# Interfaz_RS232.net
KiCad netlist of a schematic drawn in Altium Designer
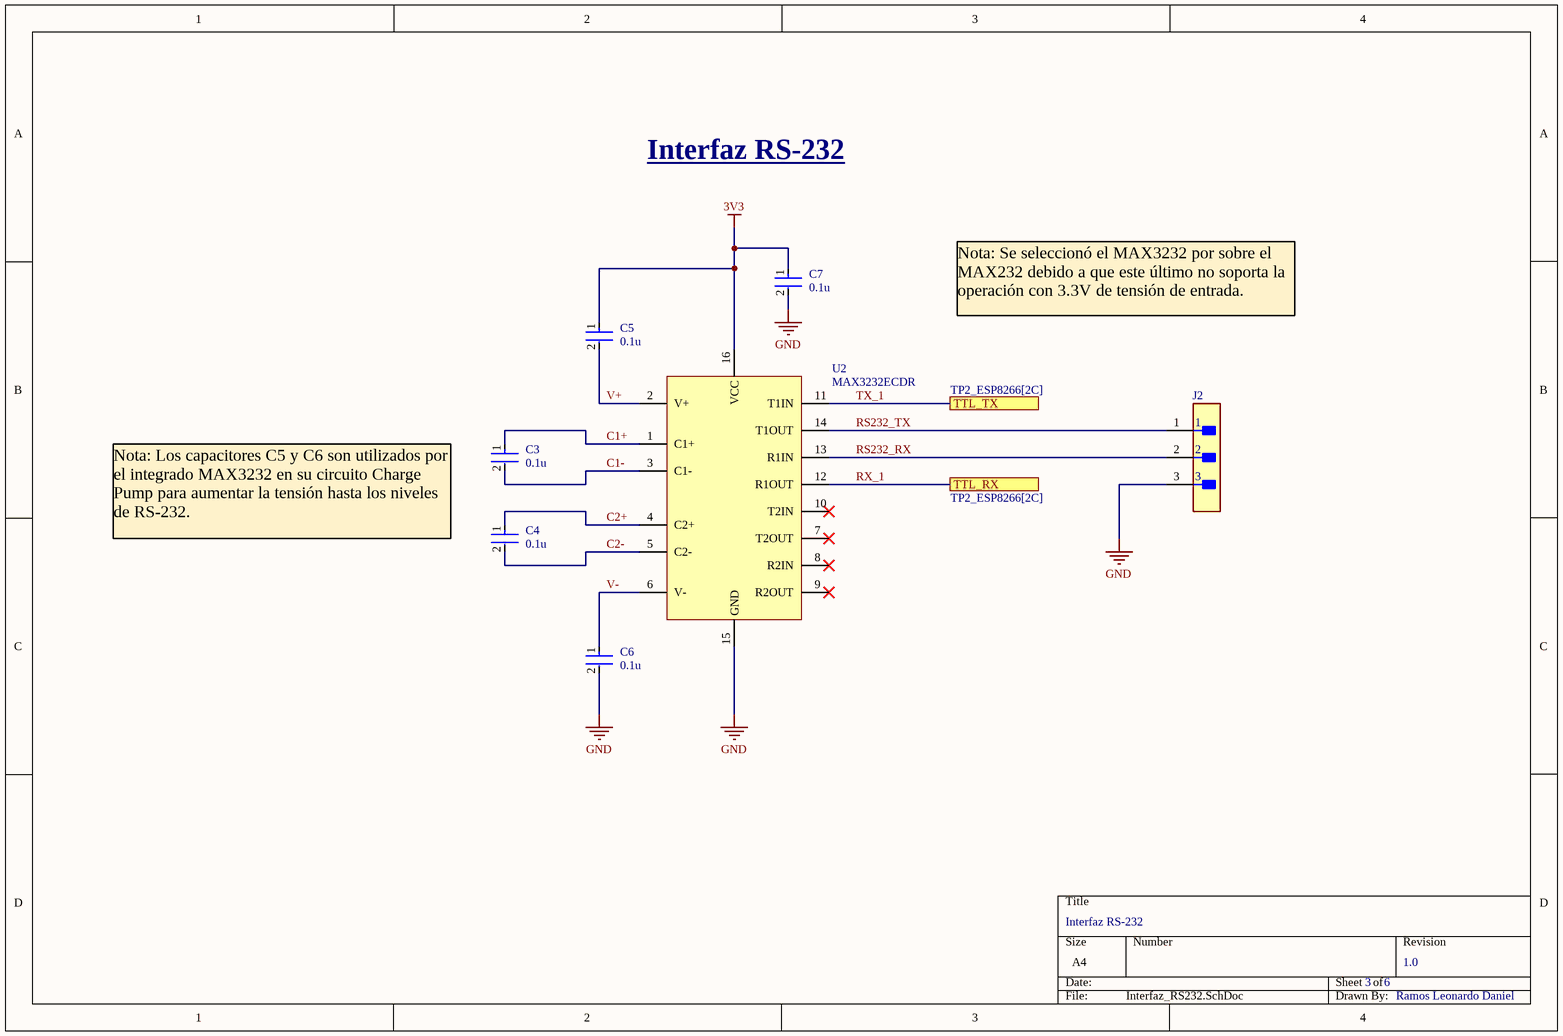
[diagram p0: Interfaz_RS232.SchDoc]

(export (version "E")
  (design (tool "Eeschema 10.0.6"))
  (components
    (comp (ref "C3")
      (value "0.1u")
      (footprint "FP-CC0805-0_85-MFG")
      (description "CAP CER 0.1UF 25V X7R 0805")
      (fields (field (name "MANUFACTURER PART NUMBER") "CC0805KRX7R8BB104") (field (name "TOLERANCE") "0.1"))
      (libsource (lib "Altium Content Vault") (part "11868f565c42a9108669ba33697ecf6"))
    )
    (comp (ref "C4")
      (value "0.1u")
      (footprint "FP-CC0805-0_85-MFG")
      (description "CAP CER 0.1UF 25V X7R 0805")
      (fields (field (name "MANUFACTURER PART NUMBER") "CC0805KRX7R8BB104") (field (name "TOLERANCE") "0.1"))
      (libsource (lib "Altium Content Vault") (part "11868f565c42a9108669ba33697ecf6"))
    )
    (comp (ref "C5")
      (value "0.1u")
      (footprint "FP-CC0805-0_85-MFG")
      (description "CAP CER 0.1UF 25V X7R 0805")
      (fields (field (name "MANUFACTURER PART NUMBER") "CC0805KRX7R8BB104") (field (name "TOLERANCE") "0.1"))
      (libsource (lib "Altium Content Vault") (part "11868f565c42a9108669ba33697ecf6"))
    )
    (comp (ref "C6")
      (value "0.1u")
      (footprint "FP-CC0805-0_85-MFG")
      (description "CAP CER 0.1UF 25V X7R 0805")
      (fields (field (name "MANUFACTURER PART NUMBER") "CC0805KRX7R8BB104") (field (name "TOLERANCE") "0.1"))
      (libsource (lib "Altium Content Vault") (part "11868f565c42a9108669ba33697ecf6"))
    )
    (comp (ref "C7")
      (value "0.1u")
      (footprint "FP-CC0805-0_85-MFG")
      (description "CAP CER 0.1UF 25V X7R 0805")
      (fields (field (name "MANUFACTURER PART NUMBER") "CC0805KRX7R8BB104") (field (name "TOLERANCE") "0.1"))
      (libsource (lib "Altium Content Vault") (part "11868f565c42a9108669ba33697ecf6"))
    )
    (comp (ref "J2")
      (value "22-11-1031")
      (footprint "FP-0022111031-MFG")
      (libsource (lib "Altium Content Vault") (part "0d3f023dd272f625e17a2be33dea85f"))
    )
    (comp (ref "U2")
      (value "MAX3232ECDR")
      (footprint "D0016A_M")
      (libsource (lib "Miscelaneos") (part "MAX3232ECDR"))
    )
  )
  (nets
    (net (code "1") (name "/C1+") (class "Default")
      (node (ref "C3") (pin "1") (pinfunction "1_1") (pintype "passive"))
      (node (ref "U2") (pin "1") (pinfunction "C1+_1") (pintype "passive"))
    )
    (net (code "2") (name "/C1-") (class "Default")
      (node (ref "C3") (pin "2") (pinfunction "2_2") (pintype "passive"))
      (node (ref "U2") (pin "3") (pinfunction "C1-_3") (pintype "passive"))
    )
    (net (code "3") (name "/C2+") (class "Default")
      (node (ref "C4") (pin "1") (pinfunction "1_1") (pintype "passive"))
      (node (ref "U2") (pin "4") (pinfunction "C2+_4") (pintype "passive"))
    )
    (net (code "4") (name "/C2-") (class "Default")
      (node (ref "C4") (pin "2") (pinfunction "2_2") (pintype "passive"))
      (node (ref "U2") (pin "5") (pinfunction "C2-_5") (pintype "passive"))
    )
    (net (code "5") (name "/RS232_RX") (class "Default")
      (node (ref "J2") (pin "2") (pinfunction "2_2") (pintype "passive"))
      (node (ref "U2") (pin "13") (pinfunction "R1IN_13") (pintype "passive"))
    )
    (net (code "6") (name "/RS232_TX") (class "Default")
      (node (ref "J2") (pin "1") (pinfunction "1_1") (pintype "passive"))
      (node (ref "U2") (pin "14") (pinfunction "T1OUT_14") (pintype "passive"))
    )
    (net (code "7") (name "/RX_1") (class "Default")
      (node (ref "U2") (pin "12") (pinfunction "R1OUT_12") (pintype "passive"))
    )
    (net (code "8") (name "/TX_1") (class "Default")
      (node (ref "U2") (pin "11") (pinfunction "T1IN_11") (pintype "passive"))
    )
    (net (code "9") (name "/V+") (class "Default")
      (node (ref "C5") (pin "2") (pinfunction "2_2") (pintype "passive"))
      (node (ref "U2") (pin "2") (pinfunction "V+_2") (pintype "passive"))
    )
    (net (code "10") (name "/V-") (class "Default")
      (node (ref "C6") (pin "1") (pinfunction "1_1") (pintype "passive"))
      (node (ref "U2") (pin "6") (pinfunction "V-_6") (pintype "passive"))
    )
    (net (code "11") (name "3V3") (class "Default")
      (node (ref "C5") (pin "1") (pinfunction "1_1") (pintype "passive"))
      (node (ref "C7") (pin "1") (pinfunction "1_1") (pintype "passive"))
      (node (ref "U2") (pin "16") (pinfunction "VCC_16") (pintype "passive"))
    )
    (net (code "12") (name "GND") (class "Default")
      (node (ref "C6") (pin "2") (pinfunction "2_2") (pintype "passive"))
      (node (ref "C7") (pin "2") (pinfunction "2_2") (pintype "passive"))
      (node (ref "J2") (pin "3") (pinfunction "3_3") (pintype "passive"))
      (node (ref "U2") (pin "15") (pinfunction "GND_15") (pintype "passive"))
    )
    (net (code "13") (name "unconnected-(U2-R2IN-Pad8)") (class "Default")
      (node (ref "U2") (pin "8") (pinfunction "R2IN_8") (pintype "passive+no_connect"))
    )
    (net (code "14") (name "unconnected-(U2-R2OUT-Pad9)") (class "Default")
      (node (ref "U2") (pin "9") (pinfunction "R2OUT_9") (pintype "passive+no_connect"))
    )
    (net (code "15") (name "unconnected-(U2-T2IN-Pad10)") (class "Default")
      (node (ref "U2") (pin "10") (pinfunction "T2IN_10") (pintype "passive+no_connect"))
    )
    (net (code "16") (name "unconnected-(U2-T2OUT-Pad7)") (class "Default")
      (node (ref "U2") (pin "7") (pinfunction "T2OUT_7") (pintype "passive+no_connect"))
    )
  )
)
